# Qwiic_Accelerometer-MMA8452Q.net
KiCad netlist of a schematic drawn in EAGLE
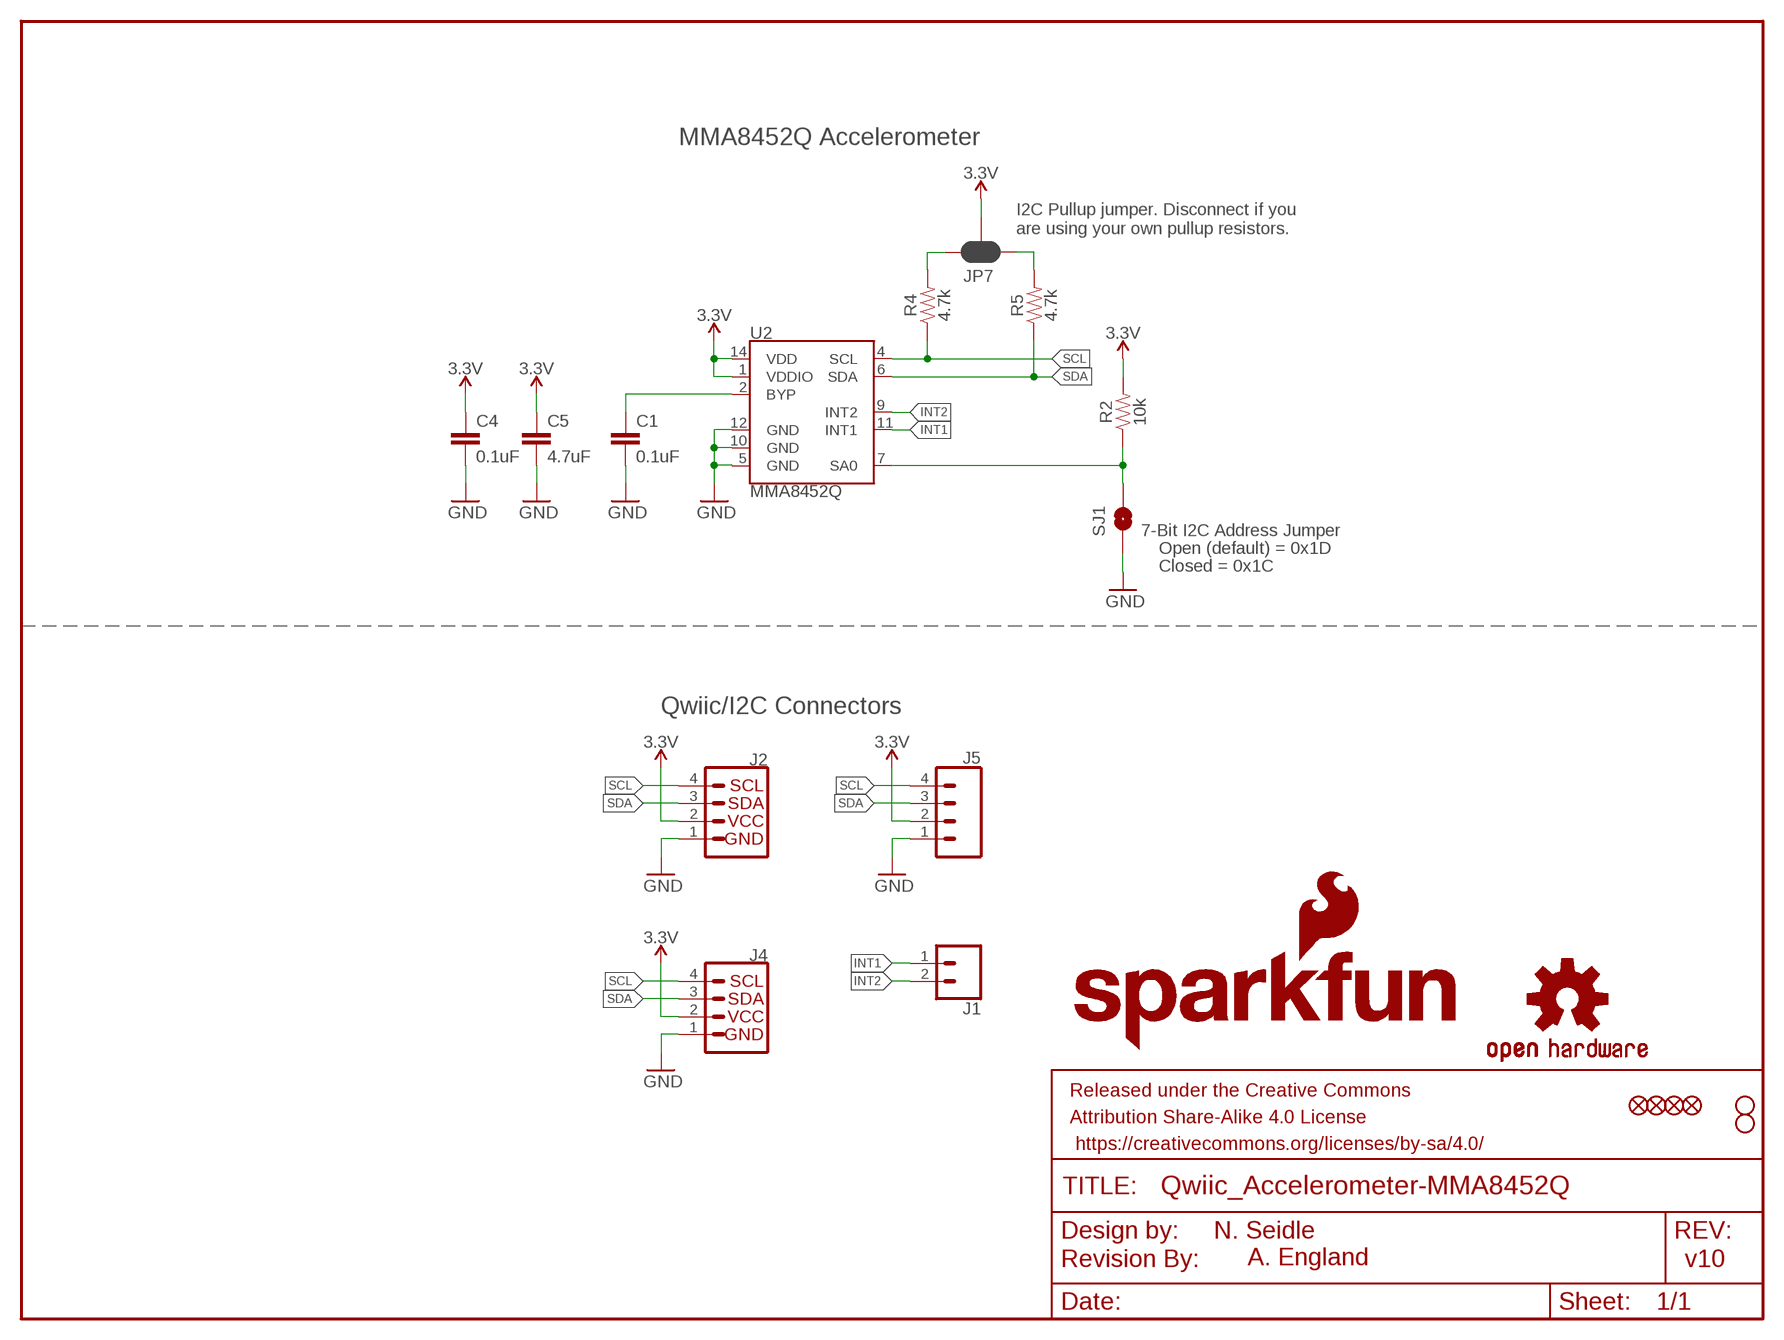
[diagram p0: schematic, sheet 1]

(export (version "E")
  (design (tool "Eeschema 10.0.6"))
  (components
    (comp (ref "C1")
      (value "0.1uF")
      (footprint "eagle-import:0603")
      (libsource (lib "eagle-import") (part "0.1UF-0603-25V-(+80/-20%)"))
    )
    (comp (ref "C4")
      (value "0.1uF")
      (footprint "eagle-import:0603")
      (libsource (lib "eagle-import") (part "0.1UF-0603-25V-(+80/-20%)"))
    )
    (comp (ref "C5")
      (value "4.7uF")
      (footprint "eagle-import:0603")
      (libsource (lib "eagle-import") (part "4.7UF0603"))
    )
    (comp (ref "FRAME1")
      (value "FRAME-LETTER")
      (footprint "eagle-import:CREATIVE_COMMONS")
      (libsource (lib "eagle-import") (part "FRAME-LETTER"))
    )
    (comp (ref "J1")
      (value "CONN_021X02_NO_SILK")
      (footprint "eagle-import:1X02_NO_SILK")
      (libsource (lib "eagle-import") (part "CONN_021X02_NO_SILK"))
    )
    (comp (ref "J2")
      (value "QWIIC_CONNECTORJS-1MM")
      (footprint "eagle-import:1X04_1MM_RA")
      (libsource (lib "eagle-import") (part "QWIIC_CONNECTORJS-1MM"))
    )
    (comp (ref "J4")
      (value "QWIIC_CONNECTORJS-1MM")
      (footprint "eagle-import:1X04_1MM_RA")
      (libsource (lib "eagle-import") (part "QWIIC_CONNECTORJS-1MM"))
    )
    (comp (ref "J5")
      (value "CONN_041X04_NO_SILK")
      (footprint "eagle-import:1X04_NO_SILK")
      (libsource (lib "eagle-import") (part "CONN_041X04_NO_SILK"))
    )
    (comp (ref "JP1")
      (value "FIDUCIALUFIDUCIAL")
      (footprint "eagle-import:MICRO-FIDUCIAL")
      (libsource (lib "eagle-import") (part "FIDUCIALUFIDUCIAL"))
    )
    (comp (ref "JP2")
      (value "FIDUCIALUFIDUCIAL")
      (footprint "eagle-import:MICRO-FIDUCIAL")
      (libsource (lib "eagle-import") (part "FIDUCIALUFIDUCIAL"))
    )
    (comp (ref "JP3")
      (value "STAND-OFF")
      (footprint "eagle-import:STAND-OFF")
      (libsource (lib "eagle-import") (part "STAND-OFF"))
    )
    (comp (ref "JP4")
      (value "STAND-OFF")
      (footprint "eagle-import:STAND-OFF")
      (libsource (lib "eagle-import") (part "STAND-OFF"))
    )
    (comp (ref "JP5")
      (value "FIDUCIALUFIDUCIAL")
      (footprint "eagle-import:MICRO-FIDUCIAL")
      (libsource (lib "eagle-import") (part "FIDUCIALUFIDUCIAL"))
    )
    (comp (ref "JP6")
      (value "FIDUCIALUFIDUCIAL")
      (footprint "eagle-import:MICRO-FIDUCIAL")
      (libsource (lib "eagle-import") (part "FIDUCIALUFIDUCIAL"))
    )
    (comp (ref "JP7")
      (value "JUMPER-SMT_3_2-NC_PASTE_SILK")
      (footprint "eagle-import:SMT-JUMPER_3_2-NC_PASTE_SILK")
      (libsource (lib "eagle-import") (part "JUMPER-SMT_3_2-NC_PASTE_SILK"))
    )
    (comp (ref "LOGO1")
      (value "OSHW-LOGOMINI")
      (footprint "eagle-import:OSHW-LOGO-MINI")
      (libsource (lib "eagle-import") (part "OSHW-LOGOMINI"))
    )
    (comp (ref "LOGO2")
      (value "SFE_LOGO_NAME_FLAME.1_INCH")
      (footprint "eagle-import:SFE_LOGO_NAME_FLAME_.1")
      (libsource (lib "eagle-import") (part "SFE_LOGO_NAME_FLAME.1_INCH"))
    )
    (comp (ref "LOGO3")
      (value "SFE_LOGO_NAME_FLAME.1_INCH")
      (footprint "eagle-import:SFE_LOGO_NAME_FLAME_.1")
      (libsource (lib "eagle-import") (part "SFE_LOGO_NAME_FLAME.1_INCH"))
    )
    (comp (ref "LOGO4")
      (value "REVISION")
      (footprint "eagle-import:REVISION")
      (libsource (lib "eagle-import") (part "REVISION"))
    )
    (comp (ref "R2")
      (value "10k")
      (footprint "eagle-import:0603")
      (libsource (lib "eagle-import") (part "10KOHM-0603-1/10W-1%"))
    )
    (comp (ref "R4")
      (value "4.7k")
      (footprint "eagle-import:0603")
      (libsource (lib "eagle-import") (part "4.7KOHM-0603-1/10W-1%"))
    )
    (comp (ref "R5")
      (value "4.7k")
      (footprint "eagle-import:0603")
      (libsource (lib "eagle-import") (part "4.7KOHM-0603-1/10W-1%"))
    )
    (comp (ref "SJ1")
      (value "SOLDERJUMPERNO")
      (footprint "eagle-import:SJ_2S-NO")
      (libsource (lib "eagle-import") (part "SOLDERJUMPERNO"))
    )
    (comp (ref "U2")
      (value "MMA8452Q")
      (footprint "eagle-import:QFN-16")
      (libsource (lib "eagle-import") (part "MMA8452Q"))
    )
  )
  (nets
    (net (code "1") (name "3.3V") (class "Default")
      (node (ref "C4") (pin "1") (pinfunction "1_1") (pintype "passive"))
      (node (ref "C5") (pin "1") (pinfunction "1_1") (pintype "passive"))
      (node (ref "J2") (pin "2") (pinfunction "2_2") (pintype "power_in"))
      (node (ref "J4") (pin "2") (pinfunction "2_2") (pintype "power_in"))
      (node (ref "J5") (pin "2") (pinfunction "2_2") (pintype "passive"))
      (node (ref "JP7") (pin "2") (pinfunction "2_2") (pintype "passive"))
      (node (ref "R2") (pin "2") (pinfunction "2_2") (pintype "passive"))
      (node (ref "U2") (pin "1") (pinfunction "VDDIO_1") (pintype "bidirectional"))
      (node (ref "U2") (pin "14") (pinfunction "VDD_14") (pintype "bidirectional"))
    )
    (net (code "2") (name "GND") (class "Default")
      (node (ref "C1") (pin "2") (pinfunction "2_2") (pintype "passive"))
      (node (ref "C4") (pin "2") (pinfunction "2_2") (pintype "passive"))
      (node (ref "C5") (pin "2") (pinfunction "2_2") (pintype "passive"))
      (node (ref "J2") (pin "1") (pinfunction "1_1") (pintype "power_in"))
      (node (ref "J4") (pin "1") (pinfunction "1_1") (pintype "power_in"))
      (node (ref "J5") (pin "1") (pinfunction "1_1") (pintype "passive"))
      (node (ref "SJ1") (pin "1") (pinfunction "1_1") (pintype "passive"))
      (node (ref "U2") (pin "10") (pinfunction "GND_10") (pintype "bidirectional"))
      (node (ref "U2") (pin "12") (pinfunction "GND_12") (pintype "bidirectional"))
      (node (ref "U2") (pin "5") (pinfunction "GND_5") (pintype "bidirectional"))
    )
    (net (code "3") (name "INT1") (class "Default")
      (node (ref "J1") (pin "1") (pinfunction "1_1") (pintype "passive"))
      (node (ref "U2") (pin "11") (pinfunction "INT1_11") (pintype "bidirectional"))
    )
    (net (code "4") (name "INT2") (class "Default")
      (node (ref "J1") (pin "2") (pinfunction "2_2") (pintype "passive"))
      (node (ref "U2") (pin "9") (pinfunction "INT2_9") (pintype "bidirectional"))
    )
    (net (code "5") (name "Net-(JP7-Pad1)") (class "Default")
      (node (ref "JP7") (pin "1") (pinfunction "1_1") (pintype "passive"))
      (node (ref "R5") (pin "2") (pinfunction "2_2") (pintype "passive"))
    )
    (net (code "6") (name "Net-(JP7-Pad3)") (class "Default")
      (node (ref "JP7") (pin "3") (pinfunction "3_3") (pintype "passive"))
      (node (ref "R4") (pin "2") (pinfunction "2_2") (pintype "passive"))
    )
    (net (code "7") (name "Net-(U2-BYP)") (class "Default")
      (node (ref "C1") (pin "1") (pinfunction "1_1") (pintype "passive"))
      (node (ref "U2") (pin "2") (pinfunction "BYP_2") (pintype "bidirectional"))
    )
    (net (code "8") (name "Net-(U2-SA0)") (class "Default")
      (node (ref "R2") (pin "1") (pinfunction "1_1") (pintype "passive"))
      (node (ref "SJ1") (pin "2") (pinfunction "2_2") (pintype "passive"))
      (node (ref "U2") (pin "7") (pinfunction "SA0_7") (pintype "bidirectional"))
    )
    (net (code "9") (name "SCL") (class "Default")
      (node (ref "J2") (pin "4") (pinfunction "4_4") (pintype "passive"))
      (node (ref "J4") (pin "4") (pinfunction "4_4") (pintype "passive"))
      (node (ref "J5") (pin "4") (pinfunction "4_4") (pintype "passive"))
      (node (ref "R4") (pin "1") (pinfunction "1_1") (pintype "passive"))
      (node (ref "U2") (pin "4") (pinfunction "SCL_4") (pintype "bidirectional"))
    )
    (net (code "10") (name "SDA") (class "Default")
      (node (ref "J2") (pin "3") (pinfunction "3_3") (pintype "passive"))
      (node (ref "J4") (pin "3") (pinfunction "3_3") (pintype "passive"))
      (node (ref "J5") (pin "3") (pinfunction "3_3") (pintype "passive"))
      (node (ref "R5") (pin "1") (pinfunction "1_1") (pintype "passive"))
      (node (ref "U2") (pin "6") (pinfunction "SDA_6") (pintype "bidirectional"))
    )
  )
)
